# Matchstick_2_0.net
KiCad netlist of a schematic drawn in EAGLE
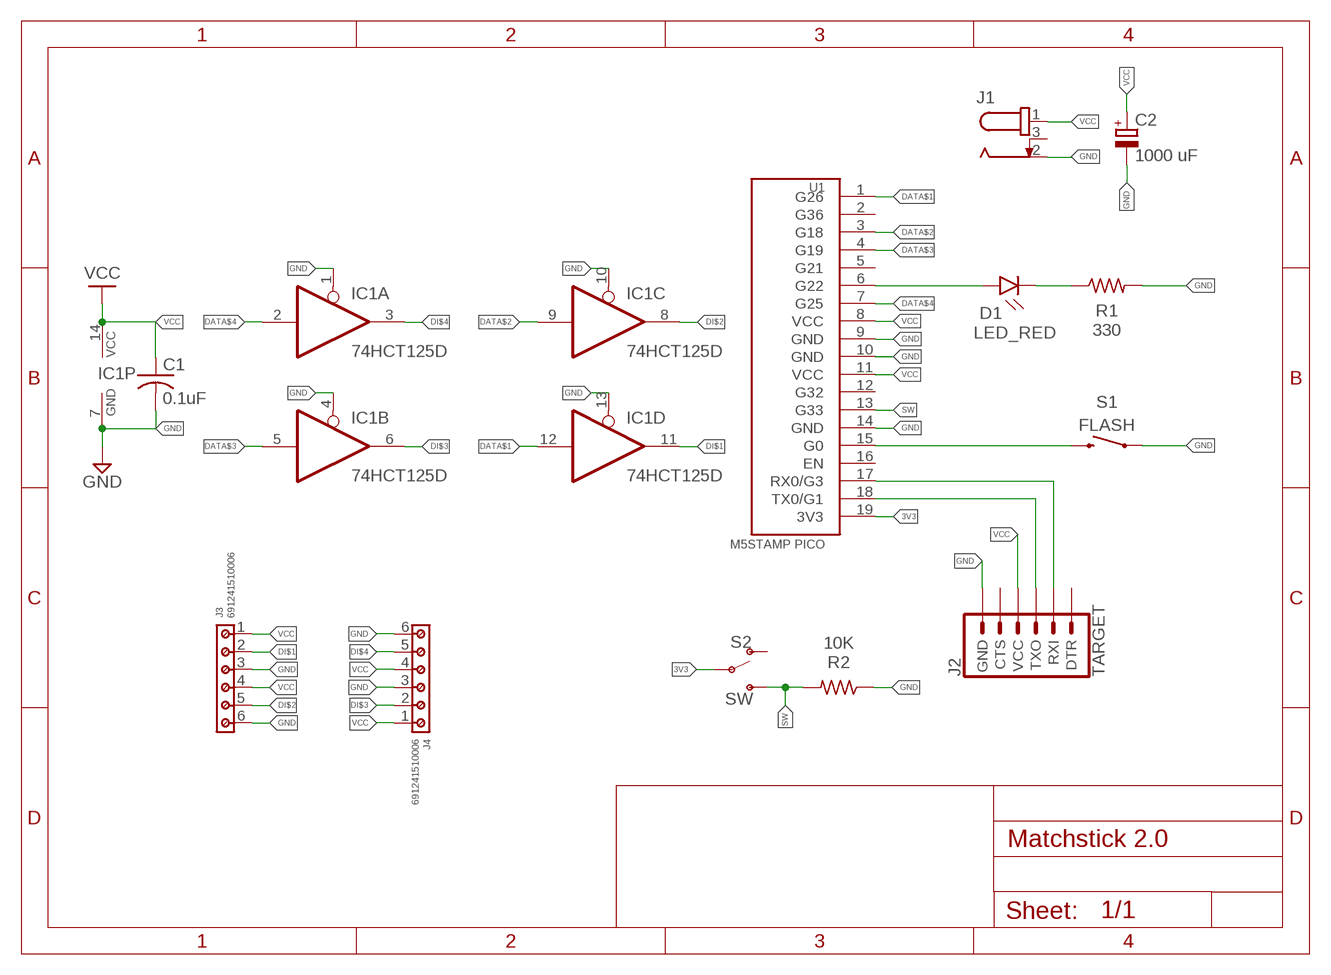
[diagram p0: schematic, sheet 1]

(export (version "E")
  (design (tool "Eeschema 10.0.6"))
  (components
    (comp (ref "C1")
      (value "0.1uF")
      (footprint "eagle-import:CAPC2012X110")
      (libsource (lib "eagle-import") (part "C-USCHIP-0805(2012-METRIC)_"))
    )
    (comp (ref "C2")
      (value "1000 uF")
      (footprint "eagle-import:CAPPRD508W65D1000H1100B")
      (libsource (lib "eagle-import") (part "C-POLRADIAL-11MM-DIA_"))
    )
    (comp (ref "D1")
      (value "LED_RED")
      (footprint "eagle-import:LEDC2012X110N_FLAT-R")
      (libsource (lib "eagle-import") (part "CHIP-FLAT-R_0805"))
    )
    (comp (ref "IC1")
      (value "74HCT125D")
      (footprint "eagle-import:SO14")
      (libsource (lib "eagle-import") (part "74125DHCT"))
    )
    (comp (ref "J1")
      (value "694106301002")
      (footprint "eagle-import:694106301002")
      (fields
        (field (name "DIGIKEY_PART_NUMBER") "732-5930-ND")
        (field (name "MANUFACTURER") "Wurth Electronics Inc.")
        (field (name "CREATED_BY") "PCBLayout.com")
      )
      (libsource (lib "eagle-import") (part "694106301002"))
    )
    (comp (ref "J2")
      (value "TARGET")
      (footprint "eagle-import:6_PIN_SERIAL_TARGET_SIDE_W_SILK")
      (libsource (lib "eagle-import") (part "6_PIN_SERIAL_TARGETSILK"))
    )
    (comp (ref "J3")
      (value "691241510006")
      (footprint "eagle-import:691241510006")
      (libsource (lib "eagle-import") (part "691241510006"))
    )
    (comp (ref "J4")
      (value "691241510006")
      (footprint "eagle-import:691241510006")
      (libsource (lib "eagle-import") (part "691241510006"))
    )
    (comp (ref "R1")
      (value "330")
      (footprint "eagle-import:RESC2012X65")
      (libsource (lib "eagle-import") (part "R-USCHIP-0805(2012-METRIC)_"))
    )
    (comp (ref "R2")
      (value "10K")
      (footprint "eagle-import:RESC2012X65")
      (libsource (lib "eagle-import") (part "R-USCHIP-0805(2012-METRIC)_"))
    )
    (comp (ref "S1")
      (value "FLASH")
      (footprint "eagle-import:TACTILE_SWITCH_SMD_5.2MM")
      (libsource (lib "eagle-import") (part "MOMENTARY-SWITCH-SPST-SMD-5.2MM"))
    )
    (comp (ref "S2")
      (value "SW")
      (footprint "eagle-import:SWITCH_SPST_SMD_A")
      (libsource (lib "eagle-import") (part "SWITCH-SPDT-SMD-RIGHT-ANGLE"))
    )
    (comp (ref "U1")
      (value "M5STAMP PICO")
      (footprint "eagle-import:M5STAMP-PICO")
      (libsource (lib "eagle-import") (part "M5STAMP-PICO"))
    )
  )
  (nets
    (net (code "1") (name "3V3") (class "Default")
      (node (ref "S2") (pin "2") (pinfunction "P_2") (pintype "passive"))
      (node (ref "U1") (pin "19") (pinfunction "3V3_19") (pintype "power_in"))
    )
    (net (code "2") (name "DATA$1") (class "Default")
      (node (ref "IC1") (pin "12") (pinfunction "I_12") (pintype "input"))
      (node (ref "U1") (pin "1") (pinfunction "G26_1") (pintype "bidirectional"))
    )
    (net (code "3") (name "DATA$2") (class "Default")
      (node (ref "IC1") (pin "9") (pinfunction "I_9") (pintype "input"))
      (node (ref "U1") (pin "3") (pinfunction "G18_3") (pintype "bidirectional"))
    )
    (net (code "4") (name "DATA$3") (class "Default")
      (node (ref "IC1") (pin "5") (pinfunction "I_5") (pintype "input"))
      (node (ref "U1") (pin "4") (pinfunction "G19_4") (pintype "bidirectional"))
    )
    (net (code "5") (name "DATA$4") (class "Default")
      (node (ref "IC1") (pin "2") (pinfunction "I_2") (pintype "input"))
      (node (ref "U1") (pin "7") (pinfunction "G25_7") (pintype "bidirectional"))
    )
    (net (code "6") (name "DI$1") (class "Default")
      (node (ref "IC1") (pin "11") (pinfunction "O_11") (pintype "tri_state"))
      (node (ref "J3") (pin "2") (pinfunction "2_2") (pintype "passive"))
    )
    (net (code "7") (name "DI$2") (class "Default")
      (node (ref "IC1") (pin "8") (pinfunction "O_8") (pintype "tri_state"))
      (node (ref "J3") (pin "5") (pinfunction "5_5") (pintype "passive"))
    )
    (net (code "8") (name "DI$3") (class "Default")
      (node (ref "IC1") (pin "6") (pinfunction "O_6") (pintype "tri_state"))
      (node (ref "J4") (pin "2") (pinfunction "2_2") (pintype "passive"))
    )
    (net (code "9") (name "DI$4") (class "Default")
      (node (ref "IC1") (pin "3") (pinfunction "O_3") (pintype "tri_state"))
      (node (ref "J4") (pin "5") (pinfunction "5_5") (pintype "passive"))
    )
    (net (code "10") (name "GND") (class "Default")
      (node (ref "C1") (pin "2") (pinfunction "2_2") (pintype "passive"))
      (node (ref "C2") (pin "2") (pinfunction "-_2") (pintype "passive"))
      (node (ref "IC1") (pin "1") (pinfunction "OE_1") (pintype "input"))
      (node (ref "IC1") (pin "10") (pinfunction "OE_10") (pintype "input"))
      (node (ref "IC1") (pin "13") (pinfunction "OE_13") (pintype "input"))
      (node (ref "IC1") (pin "4") (pinfunction "OE_4") (pintype "input"))
      (node (ref "IC1") (pin "7") (pinfunction "GND_7") (pintype "power_in"))
      (node (ref "J1") (pin "2") (pinfunction "2_2") (pintype "passive"))
      (node (ref "J2") (pin "P$6") (pinfunction "GND_P$6") (pintype "passive"))
      (node (ref "J3") (pin "3") (pinfunction "3_3") (pintype "passive"))
      (node (ref "J3") (pin "6") (pinfunction "6_6") (pintype "passive"))
      (node (ref "J4") (pin "3") (pinfunction "3_3") (pintype "passive"))
      (node (ref "J4") (pin "6") (pinfunction "6_6") (pintype "passive"))
      (node (ref "R1") (pin "2") (pinfunction "2_2") (pintype "passive"))
      (node (ref "R2") (pin "1") (pinfunction "1_1") (pintype "passive"))
      (node (ref "S1") (pin "1") (pinfunction "1_1") (pintype "passive"))
      (node (ref "U1") (pin "10") (pinfunction "GND_10") (pintype "power_in"))
      (node (ref "U1") (pin "14") (pinfunction "GND_14") (pintype "power_in"))
      (node (ref "U1") (pin "9") (pinfunction "GND_9") (pintype "power_in"))
    )
    (net (code "11") (name "Net-(D1-PadC)") (class "Default")
      (node (ref "D1") (pin "C") (pinfunction "C_C") (pintype "passive"))
      (node (ref "R1") (pin "1") (pinfunction "1_1") (pintype "passive"))
    )
    (net (code "12") (name "Net-(J2-RXI)") (class "Default")
      (node (ref "J2") (pin "P$3") (pinfunction "RXI_P$3") (pintype "passive"))
      (node (ref "U1") (pin "17") (pinfunction "RX0/G3_17") (pintype "bidirectional"))
    )
    (net (code "13") (name "Net-(J2-TXO)") (class "Default")
      (node (ref "J2") (pin "P$2") (pinfunction "TXO_P$2") (pintype "passive"))
      (node (ref "U1") (pin "18") (pinfunction "TX0/G1_18") (pintype "bidirectional"))
    )
    (net (code "14") (name "Net-(S1-2)") (class "Default")
      (node (ref "S1") (pin "3") (pinfunction "2_3") (pintype "passive"))
      (node (ref "U1") (pin "15") (pinfunction "G0_15") (pintype "bidirectional"))
    )
    (net (code "15") (name "Net-(U1-G22)") (class "Default")
      (node (ref "D1") (pin "A") (pinfunction "A_A") (pintype "passive"))
      (node (ref "U1") (pin "6") (pinfunction "G22_6") (pintype "bidirectional"))
    )
    (net (code "16") (name "SW") (class "Default")
      (node (ref "R2") (pin "2") (pinfunction "2_2") (pintype "passive"))
      (node (ref "S2") (pin "3") (pinfunction "S_3") (pintype "passive"))
      (node (ref "U1") (pin "13") (pinfunction "G33_13") (pintype "bidirectional"))
    )
    (net (code "17") (name "VCC") (class "Default")
      (node (ref "C1") (pin "1") (pinfunction "1_1") (pintype "passive"))
      (node (ref "C2") (pin "1") (pinfunction "+_1") (pintype "passive"))
      (node (ref "IC1") (pin "14") (pinfunction "VCC_14") (pintype "power_in"))
      (node (ref "J1") (pin "1") (pinfunction "1_1") (pintype "passive"))
      (node (ref "J2") (pin "P$4") (pinfunction "VCC_P$4") (pintype "passive"))
      (node (ref "J3") (pin "1") (pinfunction "1_1") (pintype "passive"))
      (node (ref "J3") (pin "4") (pinfunction "4_4") (pintype "passive"))
      (node (ref "J4") (pin "1") (pinfunction "1_1") (pintype "passive"))
      (node (ref "J4") (pin "4") (pinfunction "4_4") (pintype "passive"))
      (node (ref "U1") (pin "11") (pinfunction "VCC_11") (pintype "power_in"))
      (node (ref "U1") (pin "8") (pinfunction "VCC_8") (pintype "power_in"))
    )
    (net (code "18") (name "unconnected-(J1-Pad3)") (class "Default")
      (node (ref "J1") (pin "3") (pinfunction "3_3") (pintype "passive"))
    )
    (net (code "19") (name "unconnected-(J2-CTS-PadP$5)") (class "Default")
      (node (ref "J2") (pin "P$5") (pinfunction "CTS_P$5") (pintype "passive"))
    )
    (net (code "20") (name "unconnected-(J2-DTR-PadP$1)") (class "Default")
      (node (ref "J2") (pin "P$1") (pinfunction "DTR_P$1") (pintype "passive"))
    )
    (net (code "21") (name "unconnected-(S2-O-Pad1)") (class "Default")
      (node (ref "S2") (pin "1") (pinfunction "O_1") (pintype "passive"))
    )
    (net (code "22") (name "unconnected-(U1-EN-Pad16)") (class "Default")
      (node (ref "U1") (pin "16") (pinfunction "EN_16") (pintype "passive"))
    )
    (net (code "23") (name "unconnected-(U1-G21-Pad5)") (class "Default")
      (node (ref "U1") (pin "5") (pinfunction "G21_5") (pintype "bidirectional"))
    )
    (net (code "24") (name "unconnected-(U1-G32-Pad12)") (class "Default")
      (node (ref "U1") (pin "12") (pinfunction "G32_12") (pintype "bidirectional"))
    )
    (net (code "25") (name "unconnected-(U1-G36-Pad2)") (class "Default")
      (node (ref "U1") (pin "2") (pinfunction "G36_2") (pintype "input"))
    )
  )
)
